# Sheet2.net
KiCad netlist of a schematic drawn in Altium Designer
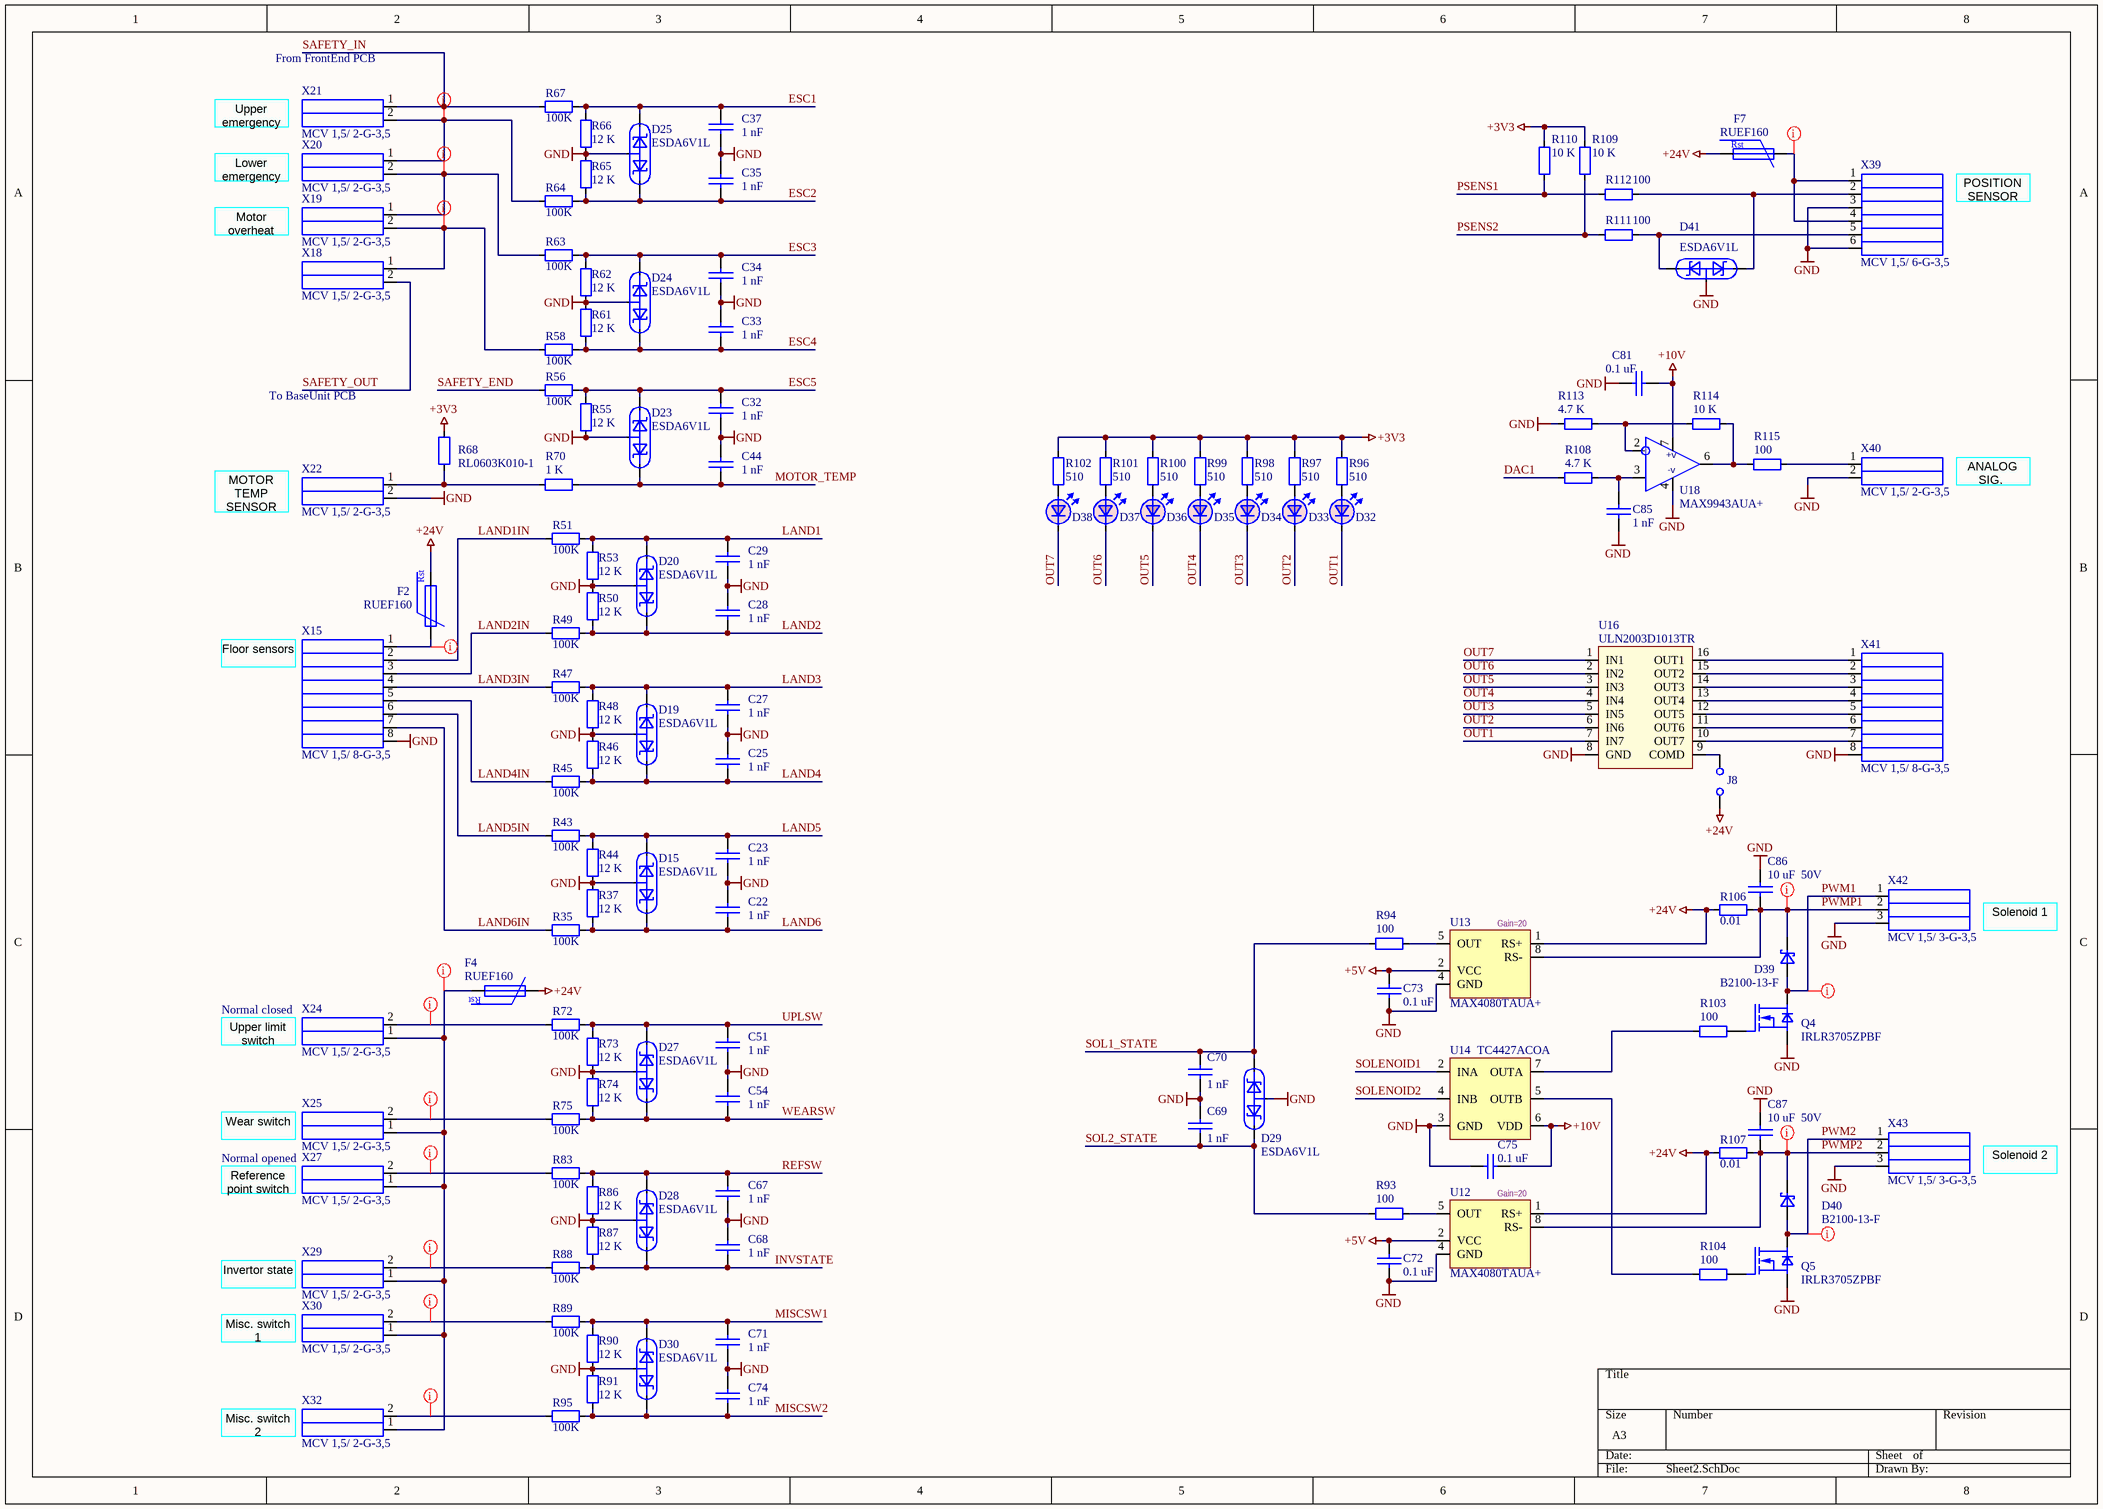
[diagram p0: Sheet2.SchDoc]

(export (version "E")
  (design (tool "Eeschema 10.0.6"))
  (components
    (comp (ref "C22")
      (value "1 nF")
      (footprint "1608[0603]")
      (description "1 nF, 50V, 10%, X7R, 0603 SMD MLC Capacitor")
      (fields (field (name "TOLERANCE") "+-10%") (field (name "MANUFACTURER") "Darfon"))
      (libsource (lib "ea_Capacitors") (part "CVNF1.0K0603"))
    )
    (comp (ref "C23")
      (value "1 nF")
      (footprint "1608[0603]")
      (description "1 nF, 50V, 10%, X7R, 0603 SMD MLC Capacitor")
      (fields (field (name "TOLERANCE") "+-10%") (field (name "MANUFACTURER") "Darfon"))
      (libsource (lib "ea_Capacitors") (part "CVNF1.0K0603"))
    )
    (comp (ref "C25")
      (value "1 nF")
      (footprint "1608[0603]")
      (description "1 nF, 50V, 10%, X7R, 0603 SMD MLC Capacitor")
      (fields (field (name "TOLERANCE") "+-10%") (field (name "MANUFACTURER") "Darfon"))
      (libsource (lib "ea_Capacitors") (part "CVNF1.0K0603"))
    )
    (comp (ref "C27")
      (value "1 nF")
      (footprint "1608[0603]")
      (description "1 nF, 50V, 10%, X7R, 0603 SMD MLC Capacitor")
      (fields (field (name "TOLERANCE") "+-10%") (field (name "MANUFACTURER") "Darfon"))
      (libsource (lib "ea_Capacitors") (part "CVNF1.0K0603"))
    )
    (comp (ref "C28")
      (value "1 nF")
      (footprint "1608[0603]")
      (description "1 nF, 50V, 10%, X7R, 0603 SMD MLC Capacitor")
      (fields (field (name "TOLERANCE") "+-10%") (field (name "MANUFACTURER") "Darfon"))
      (libsource (lib "ea_Capacitors") (part "CVNF1.0K0603"))
    )
    (comp (ref "C29")
      (value "1 nF")
      (footprint "1608[0603]")
      (description "1 nF, 50V, 10%, X7R, 0603 SMD MLC Capacitor")
      (fields (field (name "TOLERANCE") "+-10%") (field (name "MANUFACTURER") "Darfon"))
      (libsource (lib "ea_Capacitors") (part "CVNF1.0K0603"))
    )
    (comp (ref "C32")
      (value "1 nF")
      (footprint "1608[0603]")
      (description "1 nF, 50V, 10%, X7R, 0603 SMD MLC Capacitor")
      (fields (field (name "TOLERANCE") "+-10%") (field (name "MANUFACTURER") "Darfon"))
      (libsource (lib "ea_Capacitors") (part "CVNF1.0K0603"))
    )
    (comp (ref "C33")
      (value "1 nF")
      (footprint "1608[0603]")
      (description "1 nF, 50V, 10%, X7R, 0603 SMD MLC Capacitor")
      (fields (field (name "TOLERANCE") "+-10%") (field (name "MANUFACTURER") "Darfon"))
      (libsource (lib "ea_Capacitors") (part "CVNF1.0K0603"))
    )
    (comp (ref "C34")
      (value "1 nF")
      (footprint "1608[0603]")
      (description "1 nF, 50V, 10%, X7R, 0603 SMD MLC Capacitor")
      (fields (field (name "TOLERANCE") "+-10%") (field (name "MANUFACTURER") "Darfon"))
      (libsource (lib "ea_Capacitors") (part "CVNF1.0K0603"))
    )
    (comp (ref "C35")
      (value "1 nF")
      (footprint "1608[0603]")
      (description "1 nF, 50V, 10%, X7R, 0603 SMD MLC Capacitor")
      (fields (field (name "TOLERANCE") "+-10%") (field (name "MANUFACTURER") "Darfon"))
      (libsource (lib "ea_Capacitors") (part "CVNF1.0K0603"))
    )
    (comp (ref "C37")
      (value "1 nF")
      (footprint "1608[0603]")
      (description "1 nF, 50V, 10%, X7R, 0603 SMD MLC Capacitor")
      (fields (field (name "TOLERANCE") "+-10%") (field (name "MANUFACTURER") "Darfon"))
      (libsource (lib "ea_Capacitors") (part "CVNF1.0K0603"))
    )
    (comp (ref "C44")
      (value "1 nF")
      (footprint "1608[0603]")
      (description "1 nF, 50V, 10%, X7R, 0603 SMD MLC Capacitor")
      (fields (field (name "TOLERANCE") "+-10%") (field (name "MANUFACTURER") "Darfon"))
      (libsource (lib "ea_Capacitors") (part "CVNF1.0K0603"))
    )
    (comp (ref "C51")
      (value "1 nF")
      (footprint "1608[0603]")
      (description "1 nF, 50V, 10%, X7R, 0603 SMD MLC Capacitor")
      (fields (field (name "TOLERANCE") "+-10%") (field (name "MANUFACTURER") "Darfon"))
      (libsource (lib "ea_Capacitors") (part "CVNF1.0K0603"))
    )
    (comp (ref "C54")
      (value "1 nF")
      (footprint "1608[0603]")
      (description "1 nF, 50V, 10%, X7R, 0603 SMD MLC Capacitor")
      (fields (field (name "TOLERANCE") "+-10%") (field (name "MANUFACTURER") "Darfon"))
      (libsource (lib "ea_Capacitors") (part "CVNF1.0K0603"))
    )
    (comp (ref "C67")
      (value "1 nF")
      (footprint "1608[0603]")
      (description "1 nF, 50V, 10%, X7R, 0603 SMD MLC Capacitor")
      (fields (field (name "TOLERANCE") "+-10%") (field (name "MANUFACTURER") "Darfon"))
      (libsource (lib "ea_Capacitors") (part "CVNF1.0K0603"))
    )
    (comp (ref "C68")
      (value "1 nF")
      (footprint "1608[0603]")
      (description "1 nF, 50V, 10%, X7R, 0603 SMD MLC Capacitor")
      (fields (field (name "TOLERANCE") "+-10%") (field (name "MANUFACTURER") "Darfon"))
      (libsource (lib "ea_Capacitors") (part "CVNF1.0K0603"))
    )
    (comp (ref "C69")
      (value "1 nF")
      (footprint "1608[0603]")
      (description "1 nF, 50V, 10%, X7R, 0603 SMD MLC Capacitor")
      (fields (field (name "TOLERANCE") "+-10%") (field (name "MANUFACTURER") "Darfon"))
      (libsource (lib "ea_Capacitors") (part "CVNF1.0K0603"))
    )
    (comp (ref "C70")
      (value "1 nF")
      (footprint "1608[0603]")
      (description "1 nF, 50V, 10%, X7R, 0603 SMD MLC Capacitor")
      (fields (field (name "TOLERANCE") "+-10%") (field (name "MANUFACTURER") "Darfon"))
      (libsource (lib "ea_Capacitors") (part "CVNF1.0K0603"))
    )
    (comp (ref "C71")
      (value "1 nF")
      (footprint "1608[0603]")
      (description "1 nF, 50V, 10%, X7R, 0603 SMD MLC Capacitor")
      (fields (field (name "TOLERANCE") "+-10%") (field (name "MANUFACTURER") "Darfon"))
      (libsource (lib "ea_Capacitors") (part "CVNF1.0K0603"))
    )
    (comp (ref "C72")
      (value "0.1 uF")
      (footprint "1608[0603]")
      (description "0.1 uF, 25V, 10% , X7R,  0603 SMD MLC Capacitor")
      (fields (field (name "TOLERANCE") "10%") (field (name "MANUFACTURER") "SAMSUNG"))
      (libsource (lib "ea_Capacitors") (part "CVNF100K0603-25"))
    )
    (comp (ref "C73")
      (value "0.1 uF")
      (footprint "1608[0603]")
      (description "0.1 uF, 25V, 10% , X7R,  0603 SMD MLC Capacitor")
      (fields (field (name "TOLERANCE") "10%") (field (name "MANUFACTURER") "SAMSUNG"))
      (libsource (lib "ea_Capacitors") (part "CVNF100K0603-25"))
    )
    (comp (ref "C74")
      (value "1 nF")
      (footprint "1608[0603]")
      (description "1 nF, 50V, 10%, X7R, 0603 SMD MLC Capacitor")
      (fields (field (name "TOLERANCE") "+-10%") (field (name "MANUFACTURER") "Darfon"))
      (libsource (lib "ea_Capacitors") (part "CVNF1.0K0603"))
    )
    (comp (ref "C75")
      (value "0.1 uF")
      (footprint "1608[0603]")
      (description "0.1 uF, 25V, 10% , X7R,  0603 SMD MLC Capacitor")
      (fields (field (name "TOLERANCE") "10%") (field (name "MANUFACTURER") "SAMSUNG"))
      (libsource (lib "ea_Capacitors") (part "CVNF100K0603-25"))
    )
    (comp (ref "C81")
      (value "0.1 uF")
      (footprint "1608[0603]")
      (description "0.1 uF, 25V, 10% , X7R,  0603 SMD MLC Capacitor")
      (fields (field (name "TOLERANCE") "10%") (field (name "MANUFACTURER") "SAMSUNG"))
      (libsource (lib "ea_Capacitors") (part "CVNF100K0603-25"))
    )
    (comp (ref "C85")
      (value "1 nF")
      (footprint "1608[0603]")
      (description "1 nF, 50V, 10%, X7R, 0603 SMD MLC Capacitor")
      (fields (field (name "TOLERANCE") "+-10%") (field (name "MANUFACTURER") "Darfon"))
      (libsource (lib "ea_Capacitors") (part "CVNF1.0K0603"))
    )
    (comp (ref "C86")
      (value "10 uF")
      (footprint "3225[1210]")
      (description "10uF, 50V, 20%, Y5V (F), 1210")
      (fields
        (field (name "MANUFACTURER") "Taiyo Yuden")
        (field (name "TOLERANCE") "20%")
        (field (name "VOLTAGE") "50V")
      )
      (libsource (lib "ea_Capacitors") (part "GRM32DF51H106ZA01L"))
    )
    (comp (ref "C87")
      (value "10 uF")
      (footprint "3225[1210]")
      (description "10uF, 50V, 20%, Y5V (F), 1210")
      (fields
        (field (name "MANUFACTURER") "Taiyo Yuden")
        (field (name "TOLERANCE") "20%")
        (field (name "VOLTAGE") "50V")
      )
      (libsource (lib "ea_Capacitors") (part "GRM32DF51H106ZA01L"))
    )
    (comp (ref "D15")
      (value "ESDA6V1L")
      (footprint "SOT23")
      (description "Dual transil array for ESD, 6.1 V, 300 W")
      (fields (field (name "MANUFACTURER") "Micro Commercial Co") (field (name "PARTNUM") "ESDA6V1L-TPCT-ND"))
      (libsource (lib "") (part "ESDA6V1L_1"))
    )
    (comp (ref "D19")
      (value "ESDA6V1L")
      (footprint "SOT23")
      (description "Dual transil array for ESD, 6.1 V, 300 W")
      (fields (field (name "MANUFACTURER") "Micro Commercial Co") (field (name "PARTNUM") "ESDA6V1L-TPCT-ND"))
      (libsource (lib "") (part "ESDA6V1L_1"))
    )
    (comp (ref "D20")
      (value "ESDA6V1L")
      (footprint "SOT23")
      (description "Dual transil array for ESD, 6.1 V, 300 W")
      (fields (field (name "MANUFACTURER") "Micro Commercial Co") (field (name "PARTNUM") "ESDA6V1L-TPCT-ND"))
      (libsource (lib "") (part "ESDA6V1L_1"))
    )
    (comp (ref "D23")
      (value "ESDA6V1L")
      (footprint "SOT23")
      (description "Dual transil array for ESD, 6.1 V, 300 W")
      (fields (field (name "MANUFACTURER") "Micro Commercial Co") (field (name "PARTNUM") "ESDA6V1L-TPCT-ND"))
      (libsource (lib "") (part "ESDA6V1L_1"))
    )
    (comp (ref "D24")
      (value "ESDA6V1L")
      (footprint "SOT23")
      (description "Dual transil array for ESD, 6.1 V, 300 W")
      (fields (field (name "MANUFACTURER") "Micro Commercial Co") (field (name "PARTNUM") "ESDA6V1L-TPCT-ND"))
      (libsource (lib "") (part "ESDA6V1L_1"))
    )
    (comp (ref "D25")
      (value "ESDA6V1L")
      (footprint "SOT23")
      (description "Dual transil array for ESD, 6.1 V, 300 W")
      (fields (field (name "MANUFACTURER") "Micro Commercial Co") (field (name "PARTNUM") "ESDA6V1L-TPCT-ND"))
      (libsource (lib "") (part "ESDA6V1L_1"))
    )
    (comp (ref "D27")
      (value "ESDA6V1L")
      (footprint "SOT23")
      (description "Dual transil array for ESD, 6.1 V, 300 W")
      (fields (field (name "MANUFACTURER") "Micro Commercial Co") (field (name "PARTNUM") "ESDA6V1L-TPCT-ND"))
      (libsource (lib "*") (part "ESDA6V1L"))
    )
    (comp (ref "D28")
      (value "ESDA6V1L")
      (footprint "SOT23")
      (description "Dual transil array for ESD, 6.1 V, 300 W")
      (fields (field (name "MANUFACTURER") "Micro Commercial Co") (field (name "PARTNUM") "ESDA6V1L-TPCT-ND"))
      (libsource (lib "*") (part "ESDA6V1L"))
    )
    (comp (ref "D29")
      (value "ESDA6V1L")
      (footprint "SOT23")
      (description "Dual transil array for ESD, 6.1 V, 300 W")
      (fields (field (name "MANUFACTURER") "Micro Commercial Co") (field (name "PARTNUM") "ESDA6V1L-TPCT-ND"))
      (libsource (lib "*") (part "ESDA6V1L"))
    )
    (comp (ref "D30")
      (value "ESDA6V1L")
      (footprint "SOT23")
      (description "Dual transil array for ESD, 6.1 V, 300 W")
      (fields (field (name "MANUFACTURER") "Micro Commercial Co") (field (name "PARTNUM") "ESDA6V1L-TPCT-ND"))
      (libsource (lib "*") (part "ESDA6V1L"))
    )
    (comp (ref "D32")
      (value "SML-211UTT86")
      (footprint "0805 LED")
      (description "0805 red LED, hibright, 2 mA, 1.8V, 130°")
      (fields (field (name "MANUFACTURER") "Rohm") (field (name "PARTNUM") "511-1292-1-ND"))
      (libsource (lib "ea_Indicators") (part "SML-211UTT86"))
    )
    (comp (ref "D33")
      (value "SML-211UTT86")
      (footprint "0805 LED")
      (description "0805 red LED, hibright, 2 mA, 1.8V, 130°")
      (fields (field (name "MANUFACTURER") "Rohm") (field (name "PARTNUM") "511-1292-1-ND"))
      (libsource (lib "ea_Indicators") (part "SML-211UTT86"))
    )
    (comp (ref "D34")
      (value "SML-211UTT86")
      (footprint "0805 LED")
      (description "0805 red LED, hibright, 2 mA, 1.8V, 130°")
      (fields (field (name "MANUFACTURER") "Rohm") (field (name "PARTNUM") "511-1292-1-ND"))
      (libsource (lib "ea_Indicators") (part "SML-211UTT86"))
    )
    (comp (ref "D35")
      (value "SML-211UTT86")
      (footprint "0805 LED")
      (description "0805 red LED, hibright, 2 mA, 1.8V, 130°")
      (fields (field (name "MANUFACTURER") "Rohm") (field (name "PARTNUM") "511-1292-1-ND"))
      (libsource (lib "ea_Indicators") (part "SML-211UTT86"))
    )
    (comp (ref "D36")
      (value "SML-211UTT86")
      (footprint "0805 LED")
      (description "0805 red LED, hibright, 2 mA, 1.8V, 130°")
      (fields (field (name "MANUFACTURER") "Rohm") (field (name "PARTNUM") "511-1292-1-ND"))
      (libsource (lib "ea_Indicators") (part "SML-211UTT86"))
    )
    (comp (ref "D37")
      (value "SML-211UTT86")
      (footprint "0805 LED")
      (description "0805 red LED, hibright, 2 mA, 1.8V, 130°")
      (fields (field (name "MANUFACTURER") "Rohm") (field (name "PARTNUM") "511-1292-1-ND"))
      (libsource (lib "ea_Indicators") (part "SML-211UTT86"))
    )
    (comp (ref "D38")
      (value "SML-211UTT86")
      (footprint "0805 LED")
      (description "0805 red LED, hibright, 2 mA, 1.8V, 130°")
      (fields (field (name "MANUFACTURER") "Rohm") (field (name "PARTNUM") "511-1292-1-ND"))
      (libsource (lib "ea_Indicators") (part "SML-211UTT86"))
    )
    (comp (ref "D39")
      (value "B2100-13-F")
      (footprint "SMB ST")
      (description "DIODE SCHOTTKY 100V 2A SMB")
      (fields (field (name "MANUFACTURER") "Diodes Inc") (field (name "PARTNUM") "B2100-FDICT-ND"))
      (libsource (lib "ea_Diodes") (part "B2100-13-F"))
    )
    (comp (ref "D40")
      (value "B2100-13-F")
      (footprint "SMB ST")
      (description "DIODE SCHOTTKY 100V 2A SMB")
      (fields (field (name "MANUFACTURER") "Diodes Inc") (field (name "PARTNUM") "B2100-FDICT-ND"))
      (libsource (lib "ea_Diodes") (part "B2100-13-F"))
    )
    (comp (ref "D41")
      (value "ESDA6V1L")
      (footprint "SOT23")
      (description "Dual transil array for ESD, 6.1 V, 300 W")
      (fields (field (name "MANUFACTURER") "Micro Commercial Co") (field (name "PARTNUM") "ESDA6V1L-TPCT-ND"))
      (libsource (lib "*") (part "ESDA6V1L"))
    )
    (comp (ref "F2")
      (value "RUEF160")
      (footprint "RUE160")
      (description "RUEF160 - POLYSWITCH, RADIAL, 1.6A")
      (fields (field (name "MANUFACTURER") "RAYCHEM") (field (name "PARTNUM") "RUEF160-ND"))
      (libsource (lib "ea_Fuses") (part "RUEF160"))
    )
    (comp (ref "F4")
      (value "RUEF160")
      (footprint "RUE160")
      (description "RUEF160 - POLYSWITCH, RADIAL, 1.6A")
      (fields (field (name "MANUFACTURER") "RAYCHEM") (field (name "PARTNUM") "RUEF160-ND"))
      (libsource (lib "ea_Fuses") (part "RUEF160"))
    )
    (comp (ref "F7")
      (value "RUEF160")
      (footprint "RUE160")
      (description "RUEF160 - POLYSWITCH, RADIAL, 1.6A")
      (fields (field (name "MANUFACTURER") "RAYCHEM") (field (name "PARTNUM") "RUEF160-ND"))
      (libsource (lib "ea_Fuses") (part "RUEF160"))
    )
    (comp (ref "J8")
      (value "PH1-02-TA-HT")
      (footprint "HDR1X2V")
      (description "2 Pos. 2.54 mm Single Row Through Hole Straight Pin Header")
      (fields (field (name "MANUFACTURER") "ADAM TECH"))
      (libsource (lib "ea_Commutation") (part "Jumper"))
    )
    (comp (ref "Q4")
      (value "IRLR3705ZPBF")
      (footprint "DPAK TO-252")
      (description "MOSFET N-CH 55V 42A DPAK")
      (fields
        (field (name "MANUFACTURER") "International Rectifier")
        (field (name "PARTNUM") "IRLR3705ZPBF-ND")
      )
      (libsource (lib "ea_MOSFET_&_drivers") (part "IRLR3705ZPBF"))
    )
    (comp (ref "Q5")
      (value "IRLR3705ZPBF")
      (footprint "DPAK TO-252")
      (description "MOSFET N-CH 55V 42A DPAK")
      (fields
        (field (name "MANUFACTURER") "International Rectifier")
        (field (name "PARTNUM") "IRLR3705ZPBF-ND")
      )
      (libsource (lib "ea_MOSFET_&_drivers") (part "IRLR3705ZPBF"))
    )
    (comp (ref "R35")
      (value "100K")
      (footprint "3216[1206]")
      (description "100K, 1%,  1206,  200v,  SMD 1206")
      (fields (field (name "MANUFACTURER") "Panasonic") (field (name "TOLERANCE") "1%"))
      (libsource (lib "ea_Resistors") (part "CRCW1206100KFKEA"))
    )
    (comp (ref "R37")
      (value "12 K")
      (footprint "0603")
      (description "12 K, 1%, 0603, SMD Resistor, Taped")
      (fields (field (name "MANUFACTURER") "Vishay") (field (name "TOLERANCE") "1%"))
      (libsource (lib "ea_Resistors") (part "RL0603K012-1"))
    )
    (comp (ref "R43")
      (value "100K")
      (footprint "3216[1206]")
      (description "100K, 1%,  1206,  200v,  SMD 1206")
      (fields (field (name "MANUFACTURER") "Panasonic") (field (name "TOLERANCE") "1%"))
      (libsource (lib "ea_Resistors") (part "CRCW1206100KFKEA"))
    )
    (comp (ref "R44")
      (value "12 K")
      (footprint "0603")
      (description "12 K, 1%, 0603, SMD Resistor, Taped")
      (fields (field (name "MANUFACTURER") "Vishay") (field (name "TOLERANCE") "1%"))
      (libsource (lib "ea_Resistors") (part "RL0603K012-1"))
    )
    (comp (ref "R45")
      (value "100K")
      (footprint "3216[1206]")
      (description "100K, 1%,  1206,  200v,  SMD 1206")
      (fields (field (name "MANUFACTURER") "Panasonic") (field (name "TOLERANCE") "1%"))
      (libsource (lib "ea_Resistors") (part "CRCW1206100KFKEA"))
    )
    (comp (ref "R46")
      (value "12 K")
      (footprint "0603")
      (description "12 K, 1%, 0603, SMD Resistor, Taped")
      (fields (field (name "MANUFACTURER") "Vishay") (field (name "TOLERANCE") "1%"))
      (libsource (lib "ea_Resistors") (part "RL0603K012-1"))
    )
    (comp (ref "R47")
      (value "100K")
      (footprint "3216[1206]")
      (description "100K, 1%,  1206,  200v,  SMD 1206")
      (fields (field (name "MANUFACTURER") "Panasonic") (field (name "TOLERANCE") "1%"))
      (libsource (lib "ea_Resistors") (part "CRCW1206100KFKEA"))
    )
    (comp (ref "R48")
      (value "12 K")
      (footprint "0603")
      (description "12 K, 1%, 0603, SMD Resistor, Taped")
      (fields (field (name "MANUFACTURER") "Vishay") (field (name "TOLERANCE") "1%"))
      (libsource (lib "ea_Resistors") (part "RL0603K012-1"))
    )
    (comp (ref "R49")
      (value "100K")
      (footprint "3216[1206]")
      (description "100K, 1%,  1206,  200v,  SMD 1206")
      (fields (field (name "MANUFACTURER") "Panasonic") (field (name "TOLERANCE") "1%"))
      (libsource (lib "ea_Resistors") (part "CRCW1206100KFKEA"))
    )
    (comp (ref "R50")
      (value "12 K")
      (footprint "0603")
      (description "12 K, 1%, 0603, SMD Resistor, Taped")
      (fields (field (name "MANUFACTURER") "Vishay") (field (name "TOLERANCE") "1%"))
      (libsource (lib "ea_Resistors") (part "RL0603K012-1"))
    )
    (comp (ref "R51")
      (value "100K")
      (footprint "3216[1206]")
      (description "100K, 1%,  1206,  200v,  SMD 1206")
      (fields (field (name "MANUFACTURER") "Panasonic") (field (name "TOLERANCE") "1%"))
      (libsource (lib "ea_Resistors") (part "CRCW1206100KFKEA"))
    )
    (comp (ref "R53")
      (value "12 K")
      (footprint "0603")
      (description "12 K, 1%, 0603, SMD Resistor, Taped")
      (fields (field (name "MANUFACTURER") "Vishay") (field (name "TOLERANCE") "1%"))
      (libsource (lib "ea_Resistors") (part "RL0603K012-1"))
    )
    (comp (ref "R55")
      (value "12 K")
      (footprint "0603")
      (description "12 K, 1%, 0603, SMD Resistor, Taped")
      (fields (field (name "MANUFACTURER") "Vishay") (field (name "TOLERANCE") "1%"))
      (libsource (lib "ea_Resistors") (part "RL0603K012-1"))
    )
    (comp (ref "R56")
      (value "100K")
      (footprint "3216[1206]")
      (description "100K, 1%,  1206,  200v,  SMD 1206")
      (fields (field (name "MANUFACTURER") "Panasonic") (field (name "TOLERANCE") "1%"))
      (libsource (lib "ea_Resistors") (part "CRCW1206100KFKEA"))
    )
    (comp (ref "R58")
      (value "100K")
      (footprint "3216[1206]")
      (description "100K, 1%,  1206,  200v,  SMD 1206")
      (fields (field (name "MANUFACTURER") "Panasonic") (field (name "TOLERANCE") "1%"))
      (libsource (lib "ea_Resistors") (part "CRCW1206100KFKEA"))
    )
    (comp (ref "R61")
      (value "12 K")
      (footprint "0603")
      (description "12 K, 1%, 0603, SMD Resistor, Taped")
      (fields (field (name "MANUFACTURER") "Vishay") (field (name "TOLERANCE") "1%"))
      (libsource (lib "ea_Resistors") (part "RL0603K012-1"))
    )
    (comp (ref "R62")
      (value "12 K")
      (footprint "0603")
      (description "12 K, 1%, 0603, SMD Resistor, Taped")
      (fields (field (name "MANUFACTURER") "Vishay") (field (name "TOLERANCE") "1%"))
      (libsource (lib "ea_Resistors") (part "RL0603K012-1"))
    )
    (comp (ref "R63")
      (value "100K")
      (footprint "3216[1206]")
      (description "100K, 1%,  1206,  200v,  SMD 1206")
      (fields (field (name "MANUFACTURER") "Panasonic") (field (name "TOLERANCE") "1%"))
      (libsource (lib "ea_Resistors") (part "CRCW1206100KFKEA"))
    )
    (comp (ref "R64")
      (value "100K")
      (footprint "3216[1206]")
      (description "100K, 1%,  1206,  200v,  SMD 1206")
      (fields (field (name "MANUFACTURER") "Panasonic") (field (name "TOLERANCE") "1%"))
      (libsource (lib "ea_Resistors") (part "CRCW1206100KFKEA"))
    )
    (comp (ref "R65")
      (value "12 K")
      (footprint "0603")
      (description "12 K, 1%, 0603, SMD Resistor, Taped")
      (fields (field (name "MANUFACTURER") "Vishay") (field (name "TOLERANCE") "1%"))
      (libsource (lib "ea_Resistors") (part "RL0603K012-1"))
    )
    (comp (ref "R66")
      (value "12 K")
      (footprint "0603")
      (description "12 K, 1%, 0603, SMD Resistor, Taped")
      (fields (field (name "MANUFACTURER") "Vishay") (field (name "TOLERANCE") "1%"))
      (libsource (lib "ea_Resistors") (part "RL0603K012-1"))
    )
    (comp (ref "R67")
      (value "100K")
      (footprint "3216[1206]")
      (description "100K, 1%,  1206,  200v,  SMD 1206")
      (fields (field (name "MANUFACTURER") "Panasonic") (field (name "TOLERANCE") "1%"))
      (libsource (lib "ea_Resistors") (part "CRCW1206100KFKEA"))
    )
    (comp (ref "R68")
      (value "RL0603K010-1")
      (footprint "0603")
      (description "10 K, 1%, 0603, SMD Resistor, Taped")
      (fields (field (name "MANUFACTURER") "Vishay Dale") (field (name "TOLERANCE") "1%"))
      (libsource (lib "") (part "RL0603K010-1_2"))
    )
    (comp (ref "R70")
      (value "1 K")
      (footprint "0603")
      (description "1 K, 1%, 0603, SMD Resistor, Taped")
      (fields (field (name "MANUFACTURER") "YAGEO AMERICA CORPORATION") (field (name "TOLERANCE") "1%"))
      (libsource (lib "ea_Resistors") (part "RL0603K001-1"))
    )
    (comp (ref "R72")
      (value "100K")
      (footprint "3216[1206]")
      (description "100K, 1%,  1206,  200v,  SMD 1206")
      (fields (field (name "MANUFACTURER") "Panasonic") (field (name "TOLERANCE") "1%"))
      (libsource (lib "ea_Resistors") (part "CRCW1206100KFKEA"))
    )
    (comp (ref "R73")
      (value "12 K")
      (footprint "0603")
      (description "12 K, 1%, 0603, SMD Resistor, Taped")
      (fields (field (name "MANUFACTURER") "Vishay") (field (name "TOLERANCE") "1%"))
      (libsource (lib "ea_Resistors") (part "RL0603K012-1"))
    )
    (comp (ref "R74")
      (value "12 K")
      (footprint "0603")
      (description "12 K, 1%, 0603, SMD Resistor, Taped")
      (fields (field (name "MANUFACTURER") "Vishay") (field (name "TOLERANCE") "1%"))
      (libsource (lib "ea_Resistors") (part "RL0603K012-1"))
    )
    (comp (ref "R75")
      (value "100K")
      (footprint "3216[1206]")
      (description "100K, 1%,  1206,  200v,  SMD 1206")
      (fields (field (name "MANUFACTURER") "Panasonic") (field (name "TOLERANCE") "1%"))
      (libsource (lib "ea_Resistors") (part "CRCW1206100KFKEA"))
    )
    (comp (ref "R83")
      (value "100K")
      (footprint "3216[1206]")
      (description "100K, 1%,  1206,  200v,  SMD 1206")
      (fields (field (name "MANUFACTURER") "Panasonic") (field (name "TOLERANCE") "1%"))
      (libsource (lib "ea_Resistors") (part "CRCW1206100KFKEA"))
    )
    (comp (ref "R86")
      (value "12 K")
      (footprint "0603")
      (description "12 K, 1%, 0603, SMD Resistor, Taped")
      (fields (field (name "MANUFACTURER") "Vishay") (field (name "TOLERANCE") "1%"))
      (libsource (lib "ea_Resistors") (part "RL0603K012-1"))
    )
    (comp (ref "R87")
      (value "12 K")
      (footprint "0603")
      (description "12 K, 1%, 0603, SMD Resistor, Taped")
      (fields (field (name "MANUFACTURER") "Vishay") (field (name "TOLERANCE") "1%"))
      (libsource (lib "ea_Resistors") (part "RL0603K012-1"))
    )
    (comp (ref "R88")
      (value "100K")
      (footprint "3216[1206]")
      (description "100K, 1%,  1206,  200v,  SMD 1206")
      (fields (field (name "MANUFACTURER") "Panasonic") (field (name "TOLERANCE") "1%"))
      (libsource (lib "ea_Resistors") (part "CRCW1206100KFKEA"))
    )
    (comp (ref "R89")
      (value "100K")
      (footprint "3216[1206]")
      (description "100K, 1%,  1206,  200v,  SMD 1206")
      (fields (field (name "MANUFACTURER") "Panasonic") (field (name "TOLERANCE") "1%"))
      (libsource (lib "ea_Resistors") (part "CRCW1206100KFKEA"))
    )
    (comp (ref "R90")
      (value "12 K")
      (footprint "0603")
      (description "12 K, 1%, 0603, SMD Resistor, Taped")
      (fields (field (name "MANUFACTURER") "Vishay") (field (name "TOLERANCE") "1%"))
      (libsource (lib "ea_Resistors") (part "RL0603K012-1"))
    )
    (comp (ref "R91")
      (value "12 K")
      (footprint "0603")
      (description "12 K, 1%, 0603, SMD Resistor, Taped")
      (fields (field (name "MANUFACTURER") "Vishay") (field (name "TOLERANCE") "1%"))
      (libsource (lib "ea_Resistors") (part "RL0603K012-1"))
    )
    (comp (ref "R93")
      (value "100")
      (footprint "0603")
      (description "100, 1%, 0603, SMD Resistor, Taped")
      (fields (field (name "TOLERANCE") "1%") (field (name "MANUFACTURER") "PANASONIC"))
      (libsource (lib "ea_Resistors") (part "RL0603E100-1"))
    )
    (comp (ref "R94")
      (value "100")
      (footprint "0603")
      (description "100, 1%, 0603, SMD Resistor, Taped")
      (fields (field (name "TOLERANCE") "1%") (field (name "MANUFACTURER") "PANASONIC"))
      (libsource (lib "ea_Resistors") (part "RL0603E100-1"))
    )
    (comp (ref "R95")
      (value "100K")
      (footprint "3216[1206]")
      (description "100K, 1%,  1206,  200v,  SMD 1206")
      (fields (field (name "MANUFACTURER") "Panasonic") (field (name "TOLERANCE") "1%"))
      (libsource (lib "ea_Resistors") (part "CRCW1206100KFKEA"))
    )
    (comp (ref "R96")
      (value "510")
      (footprint "0603")
      (description "510 R, 1%, 0603, SMD Resistor, Taped")
      (fields (field (name "MANUFACTURER") "Vishay") (field (name "TOLERANCE") "1%"))
      (libsource (lib "ea_Resistors") (part "RL0603E510-1"))
    )
    (comp (ref "R97")
      (value "510")
      (footprint "0603")
      (description "510 R, 1%, 0603, SMD Resistor, Taped")
      (fields (field (name "MANUFACTURER") "Vishay") (field (name "TOLERANCE") "1%"))
      (libsource (lib "ea_Resistors") (part "RL0603E510-1"))
    )
    (comp (ref "R98")
      (value "510")
      (footprint "0603")
      (description "510 R, 1%, 0603, SMD Resistor, Taped")
      (fields (field (name "MANUFACTURER") "Vishay") (field (name "TOLERANCE") "1%"))
      (libsource (lib "ea_Resistors") (part "RL0603E510-1"))
    )
    (comp (ref "R99")
      (value "510")
      (footprint "0603")
      (description "510 R, 1%, 0603, SMD Resistor, Taped")
      (fields (field (name "MANUFACTURER") "Vishay") (field (name "TOLERANCE") "1%"))
      (libsource (lib "ea_Resistors") (part "RL0603E510-1"))
    )
    (comp (ref "R100")
      (value "510")
      (footprint "0603")
      (description "510 R, 1%, 0603, SMD Resistor, Taped")
      (fields (field (name "MANUFACTURER") "Vishay") (field (name "TOLERANCE") "1%"))
      (libsource (lib "ea_Resistors") (part "RL0603E510-1"))
    )
    (comp (ref "R101")
      (value "510")
      (footprint "0603")
      (description "510 R, 1%, 0603, SMD Resistor, Taped")
      (fields (field (name "MANUFACTURER") "Vishay") (field (name "TOLERANCE") "1%"))
      (libsource (lib "ea_Resistors") (part "RL0603E510-1"))
    )
    (comp (ref "R102")
      (value "510")
      (footprint "0603")
      (description "510 R, 1%, 0603, SMD Resistor, Taped")
      (fields (field (name "MANUFACTURER") "Vishay") (field (name "TOLERANCE") "1%"))
      (libsource (lib "ea_Resistors") (part "RL0603E510-1"))
    )
    (comp (ref "R103")
      (value "100")
      (footprint "0603")
      (description "100, 1%, 0603, SMD Resistor, Taped")
      (fields (field (name "TOLERANCE") "1%") (field (name "MANUFACTURER") "PANASONIC"))
      (libsource (lib "ea_Resistors") (part "RL0603E100-1"))
    )
    (comp (ref "R104")
      (value "100")
      (footprint "0603")
      (description "100, 1%, 0603, SMD Resistor, Taped")
      (fields (field (name "TOLERANCE") "1%") (field (name "MANUFACTURER") "PANASONIC"))
      (libsource (lib "ea_Resistors") (part "RL0603E100-1"))
    )
    (comp (ref "R106")
      (value "0.01")
      (footprint "MCS3264")
      (description "Curr.sens.res. 0.01 OHM 2W 1% , 2512 (6432 Metric)")
      (fields (field (name "MANUFACTURER") "Ohmite") (field (name "TOLERANCE") "1%"))
      (libsource (lib "ea_Resistors") (part "MCS3264R010FER"))
    )
    (comp (ref "R107")
      (value "0.01")
      (footprint "MCS3264")
      (description "Curr.sens.res. 0.01 OHM 2W 1% , 2512 (6432 Metric)")
      (fields (field (name "MANUFACTURER") "Ohmite") (field (name "TOLERANCE") "1%"))
      (libsource (lib "ea_Resistors") (part "MCS3264R010FER"))
    )
    (comp (ref "R108")
      (value "4.7 K")
      (footprint "0603")
      (description "4.7 K, 1%, 0603, SMD Resistor, Taped")
      (fields (field (name "MANUFACTURER") "Vishay") (field (name "TOLERANCE") "1%"))
      (libsource (lib "ea_Resistors") (part "RL0603K004.7-1"))
    )
    (comp (ref "R109")
      (value "10 K")
      (footprint "0603")
      (description "10 K, 1%, 0603, SMD Resistor, Taped")
      (fields (field (name "MANUFACTURER") "Vishay Dale") (field (name "TOLERANCE") "1%"))
      (libsource (lib "ea_Resistors") (part "RL0603K010-1"))
    )
    (comp (ref "R110")
      (value "10 K")
      (footprint "0603")
      (description "10 K, 1%, 0603, SMD Resistor, Taped")
      (fields (field (name "MANUFACTURER") "Vishay Dale") (field (name "TOLERANCE") "1%"))
      (libsource (lib "ea_Resistors") (part "RL0603K010-1"))
    )
    (comp (ref "R111")
      (value "100")
      (footprint "0603")
      (description "100, 1%, 0603, SMD Resistor, Taped")
      (fields (field (name "TOLERANCE") "1%") (field (name "MANUFACTURER") "PANASONIC"))
      (libsource (lib "") (part "RL0603E100-1_1"))
    )
    (comp (ref "R112")
      (value "100")
      (footprint "0603")
      (description "100, 1%, 0603, SMD Resistor, Taped")
      (fields (field (name "TOLERANCE") "1%") (field (name "MANUFACTURER") "PANASONIC"))
      (libsource (lib "") (part "RL0603E100-1_1"))
    )
    (comp (ref "R113")
      (value "4.7 K")
      (footprint "0603")
      (description "4.7 K, 1%, 0603, SMD Resistor, Taped")
      (fields (field (name "MANUFACTURER") "Vishay") (field (name "TOLERANCE") "1%"))
      (libsource (lib "ea_Resistors") (part "RL0603K004.7-1"))
    )
    (comp (ref "R114")
      (value "10 K")
      (footprint "0603")
      (description "10 K, 1%, 0603, SMD Resistor, Taped")
      (fields (field (name "MANUFACTURER") "Vishay Dale") (field (name "TOLERANCE") "1%"))
      (libsource (lib "") (part "RL0603K010-1_1"))
    )
    (comp (ref "R115")
      (value "100")
      (footprint "0603")
      (description "100, 1%, 0603, SMD Resistor, Taped")
      (fields (field (name "TOLERANCE") "1%") (field (name "MANUFACTURER") "PANASONIC"))
      (libsource (lib "") (part "RL0603E100-1_1"))
    )
    (comp (ref "U12")
      (value "MAX4080TAUA+")
      (footprint "MSOP 8")
      (description "IC OPAMP CURR SENSE 250KHZ 8UMAX")
      (fields (field (name "MANUFACTURER") "Infineon") (field (name "PARTNUM") "MAX4080TAUA+-ND"))
      (libsource (lib "ea_IC_sensors") (part "MAX4080TAUA+"))
    )
    (comp (ref "U13")
      (value "MAX4080TAUA+")
      (footprint "MSOP 8")
      (description "IC OPAMP CURR SENSE 250KHZ 8UMAX")
      (fields (field (name "MANUFACTURER") "Infineon") (field (name "PARTNUM") "MAX4080TAUA+-ND"))
      (libsource (lib "ea_IC_sensors") (part "MAX4080TAUA+"))
    )
    (comp (ref "U14")
      (value "TC4427ACOA")
      (footprint "SO-8")
      (description "MOSFET drv 1.5A dual, 4.5-18 V,   8SOIC, 0-70 C")
      (fields (field (name "MANUFACTURER") "Microchip Technology") (field (name "PARTNUM") "TC4427ACOA-ND"))
      (libsource (lib "ea_IC_registers_buffers") (part "TC4427ACOA"))
    )
    (comp (ref "U16")
      (value "ULN2003D1013TR")
      (footprint "SO-16")
      (description "TRANS 7 NPN DARL 50V 500MA 16SO")
      (fields (field (name "MANUFACTURER") "STMicroelectronics") (field (name "PARTNUM") "497-2345-1-ND"))
      (libsource (lib "ea_IC_registers_buffers") (part "ULN2003D1013TR"))
    )
    (comp (ref "U18")
      (value "MAX9943AUA+")
      (footprint "TSSOP-8")
      (description "OpAmp 2.4MHZ, 6..38V,  20 mA, 8-TSSOP")
      (fields
        (field (name "MANUFACTURER") "Maxim Integrated Products")
        (field (name "PARTNUM") "MAX9943AUA+-ND")
      )
      (libsource (lib "ea_IC_OPAmps_AnComparators") (part "MAX9943AUA+"))
    )
    (comp (ref "X15")
      (value "MCV 1,5/ 8-G-3,5")
      (footprint "mcv1.5-8-g_3.5")
      (description "HEADER, VERTICAL, 3.5MM, 8WAY")
      (fields (field (name "MANUFACTURER") "PHOENIX CONTACT") (field (name "PARTNUM") "1843664"))
      (libsource (lib "ea_Connectors") (part "MCV1.5/8-G-3.5"))
    )
    (comp (ref "X18")
      (value "MCV 1,5/ 2-G-3,5")
      (footprint "mcv1.5-2-g_3.5")
      (description "HEADER, VERTICAL, 3.5MM, 2WAY")
      (fields (field (name "MANUFACTURER") "PHOENIX CONTACT") (field (name "PARTNUM") "1843606"))
      (libsource (lib "ea_Connectors") (part "MCV1.5/2-G-3.5"))
    )
    (comp (ref "X19")
      (value "MCV 1,5/ 2-G-3,5")
      (footprint "mcv1.5-2-g_3.5")
      (description "HEADER, VERTICAL, 3.5MM, 2WAY")
      (fields (field (name "MANUFACTURER") "PHOENIX CONTACT") (field (name "PARTNUM") "1843606"))
      (libsource (lib "ea_Connectors") (part "MCV1.5/2-G-3.5"))
    )
    (comp (ref "X20")
      (value "MCV 1,5/ 2-G-3,5")
      (footprint "mcv1.5-2-g_3.5")
      (description "HEADER, VERTICAL, 3.5MM, 2WAY")
      (fields (field (name "MANUFACTURER") "PHOENIX CONTACT") (field (name "PARTNUM") "1843606"))
      (libsource (lib "ea_Connectors") (part "MCV1.5/2-G-3.5"))
    )
    (comp (ref "X21")
      (value "MCV 1,5/ 2-G-3,5")
      (footprint "mcv1.5-2-g_3.5")
      (description "HEADER, VERTICAL, 3.5MM, 2WAY")
      (fields (field (name "MANUFACTURER") "PHOENIX CONTACT") (field (name "PARTNUM") "1843606"))
      (libsource (lib "ea_Connectors") (part "MCV1.5/2-G-3.5"))
    )
    (comp (ref "X22")
      (value "MCV 1,5/ 2-G-3,5")
      (footprint "mcv1.5-2-g_3.5")
      (description "HEADER, VERTICAL, 3.5MM, 2WAY")
      (fields (field (name "MANUFACTURER") "PHOENIX CONTACT") (field (name "PARTNUM") "1843606"))
      (libsource (lib "ea_Connectors") (part "MCV1.5/2-G-3.5"))
    )
    (comp (ref "X24")
      (value "MCV 1,5/ 2-G-3,5")
      (footprint "mcv1.5-2-g_3.5")
      (description "HEADER, VERTICAL, 3.5MM, 2WAY")
      (fields (field (name "MANUFACTURER") "PHOENIX CONTACT") (field (name "PARTNUM") "1843606"))
      (libsource (lib "ea_Connectors") (part "MCV1.5/2-G-3.5"))
    )
    (comp (ref "X25")
      (value "MCV 1,5/ 2-G-3,5")
      (footprint "mcv1.5-2-g_3.5")
      (description "HEADER, VERTICAL, 3.5MM, 2WAY")
      (fields (field (name "MANUFACTURER") "PHOENIX CONTACT") (field (name "PARTNUM") "1843606"))
      (libsource (lib "ea_Connectors") (part "MCV1.5/2-G-3.5"))
    )
    (comp (ref "X27")
      (value "MCV 1,5/ 2-G-3,5")
      (footprint "mcv1.5-2-g_3.5")
      (description "HEADER, VERTICAL, 3.5MM, 2WAY")
      (fields (field (name "MANUFACTURER") "PHOENIX CONTACT") (field (name "PARTNUM") "1843606"))
      (libsource (lib "ea_Connectors") (part "MCV1.5/2-G-3.5"))
    )
    (comp (ref "X29")
      (value "MCV 1,5/ 2-G-3,5")
      (footprint "mcv1.5-2-g_3.5")
      (description "HEADER, VERTICAL, 3.5MM, 2WAY")
      (fields (field (name "MANUFACTURER") "PHOENIX CONTACT") (field (name "PARTNUM") "1843606"))
      (libsource (lib "ea_Connectors") (part "MCV1.5/2-G-3.5"))
    )
    (comp (ref "X30")
      (value "MCV 1,5/ 2-G-3,5")
      (footprint "mcv1.5-2-g_3.5")
      (description "HEADER, VERTICAL, 3.5MM, 2WAY")
      (fields (field (name "MANUFACTURER") "PHOENIX CONTACT") (field (name "PARTNUM") "1843606"))
      (libsource (lib "ea_Connectors") (part "MCV1.5/2-G-3.5"))
    )
    (comp (ref "X32")
      (value "MCV 1,5/ 2-G-3,5")
      (footprint "mcv1.5-2-g_3.5")
      (description "HEADER, VERTICAL, 3.5MM, 2WAY")
      (fields (field (name "MANUFACTURER") "PHOENIX CONTACT") (field (name "PARTNUM") "1843606"))
      (libsource (lib "ea_Connectors") (part "MCV1.5/2-G-3.5"))
    )
    (comp (ref "X39")
      (value "MCV 1,5/ 6-G-3,5")
      (footprint "mcv1.5-6-g_3.5")
      (description "HEADER, VERTICAL, 3.5MM, 6WAY")
      (fields (field (name "MANUFACTURER") "PHOENIX CONTACT") (field (name "PARTNUM") "1843648"))
      (libsource (lib "ea_Connectors") (part "MCV1.5/6-G-3.5"))
    )
    (comp (ref "X40")
      (value "MCV 1,5/ 2-G-3,5")
      (footprint "mcv1.5-2-g_3.5")
      (description "HEADER, VERTICAL, 3.5MM, 2WAY")
      (fields (field (name "MANUFACTURER") "PHOENIX CONTACT") (field (name "PARTNUM") "1843606"))
      (libsource (lib "ea_Connectors") (part "MCV1.5/2-G-3.5"))
    )
    (comp (ref "X41")
      (value "MCV 1,5/ 8-G-3,5")
      (footprint "mcv1.5-8-g_3.5")
      (description "HEADER, VERTICAL, 3.5MM, 8WAY")
      (fields (field (name "MANUFACTURER") "PHOENIX CONTACT") (field (name "PARTNUM") "1843664"))
      (libsource (lib "ea_Connectors") (part "MCV1.5/8-G-3.5"))
    )
    (comp (ref "X42")
      (value "MCV 1,5/ 3-G-3,5")
      (footprint "mcv1.5-3-g_3.5")
      (description "Header, 8 A, 160 V, 3.5 mm pitch, 3 pos")
      (fields (field (name "MANUFACTURER") "Phoenix Contact") (field (name "PARTNUM") "1843619"))
      (libsource (lib "ea_Connectors") (part "MCV1.5/3-G-3.5"))
    )
    (comp (ref "X43")
      (value "MCV 1,5/ 3-G-3,5")
      (footprint "mcv1.5-3-g_3.5")
      (description "Header, 8 A, 160 V, 3.5 mm pitch, 3 pos")
      (fields (field (name "MANUFACTURER") "Phoenix Contact") (field (name "PARTNUM") "1843619"))
      (libsource (lib "ea_Connectors") (part "MCV1.5/3-G-3.5"))
    )
  )
  (nets
    (net (code "1") (name "+3V3") (class "Default")
      (node (ref "R100") (pin "2") (pinfunction "2_2") (pintype "passive"))
      (node (ref "R101") (pin "2") (pinfunction "2_2") (pintype "passive"))
      (node (ref "R102") (pin "2") (pinfunction "2_2") (pintype "passive"))
      (node (ref "R109") (pin "2") (pinfunction "2_2") (pintype "passive"))
      (node (ref "R110") (pin "2") (pinfunction "2_2") (pintype "passive"))
      (node (ref "R68") (pin "1") (pinfunction "1_1") (pintype "passive"))
      (node (ref "R96") (pin "2") (pinfunction "2_2") (pintype "passive"))
      (node (ref "R97") (pin "2") (pinfunction "2_2") (pintype "passive"))
      (node (ref "R98") (pin "2") (pinfunction "2_2") (pintype "passive"))
      (node (ref "R99") (pin "2") (pinfunction "2_2") (pintype "passive"))
    )
    (net (code "2") (name "+5V") (class "Default")
      (node (ref "C72") (pin "2") (pinfunction "2_2") (pintype "passive"))
      (node (ref "C73") (pin "2") (pinfunction "2_2") (pintype "passive"))
      (node (ref "U12") (pin "2") (pinfunction "VCC_2") (pintype "passive"))
      (node (ref "U13") (pin "2") (pinfunction "VCC_2") (pintype "passive"))
    )
    (net (code "3") (name "+10V") (class "Default")
      (node (ref "C75") (pin "2") (pinfunction "2_2") (pintype "passive"))
      (node (ref "C81") (pin "2") (pinfunction "2_2") (pintype "passive"))
      (node (ref "U14") (pin "6") (pinfunction "VDD_6") (pintype "passive"))
      (node (ref "U18") (pin "7") (pinfunction "V+_7") (pintype "power_in"))
    )
    (net (code "4") (name "+24V") (class "Default")
      (node (ref "F2") (pin "2") (pinfunction "2_2") (pintype "passive"))
      (node (ref "F4") (pin "1") (pinfunction "1_1") (pintype "passive"))
      (node (ref "F7") (pin "2") (pinfunction "2_2") (pintype "passive"))
      (node (ref "J8") (pin "1") (pinfunction "1_1") (pintype "passive"))
      (node (ref "R106") (pin "2") (pinfunction "2_2") (pintype "passive"))
      (node (ref "R107") (pin "2") (pinfunction "2_2") (pintype "passive"))
      (node (ref "U12") (pin "1") (pinfunction "RS+_1") (pintype "passive"))
      (node (ref "U13") (pin "1") (pinfunction "RS+_1") (pintype "passive"))
    )
    (net (code "5") (name "/DAC1") (class "Default")
      (node (ref "R108") (pin "2") (pinfunction "2_2") (pintype "passive"))
    )
    (net (code "6") (name "/ESC1") (class "Default")
      (node (ref "C37") (pin "1") (pinfunction "1_1") (pintype "passive"))
      (node (ref "D25") (pin "2") (pintype "passive"))
      (node (ref "R66") (pin "2") (pinfunction "2_2") (pintype "passive"))
      (node (ref "R67") (pin "2") (pinfunction "2_2") (pintype "passive"))
    )
    (net (code "7") (name "/ESC2") (class "Default")
      (node (ref "C35") (pin "2") (pinfunction "2_2") (pintype "passive"))
      (node (ref "D25") (pin "1") (pintype "passive"))
      (node (ref "R64") (pin "2") (pinfunction "2_2") (pintype "passive"))
      (node (ref "R65") (pin "1") (pinfunction "1_1") (pintype "passive"))
    )
    (net (code "8") (name "/ESC3") (class "Default")
      (node (ref "C34") (pin "1") (pinfunction "1_1") (pintype "passive"))
      (node (ref "D24") (pin "2") (pintype "passive"))
      (node (ref "R62") (pin "2") (pinfunction "2_2") (pintype "passive"))
      (node (ref "R63") (pin "2") (pinfunction "2_2") (pintype "passive"))
    )
    (net (code "9") (name "/ESC4") (class "Default")
      (node (ref "C33") (pin "2") (pinfunction "2_2") (pintype "passive"))
      (node (ref "D24") (pin "1") (pintype "passive"))
      (node (ref "R58") (pin "2") (pinfunction "2_2") (pintype "passive"))
      (node (ref "R61") (pin "1") (pinfunction "1_1") (pintype "passive"))
    )
    (net (code "10") (name "/ESC5") (class "Default")
      (node (ref "C32") (pin "1") (pinfunction "1_1") (pintype "passive"))
      (node (ref "D23") (pin "2") (pintype "passive"))
      (node (ref "R55") (pin "2") (pinfunction "2_2") (pintype "passive"))
      (node (ref "R56") (pin "2") (pinfunction "2_2") (pintype "passive"))
    )
    (net (code "11") (name "/INVSTATE") (class "Default")
      (node (ref "C68") (pin "2") (pinfunction "2_2") (pintype "passive"))
      (node (ref "D28") (pin "2") (pintype "passive"))
      (node (ref "R87") (pin "1") (pinfunction "1_1") (pintype "passive"))
      (node (ref "R88") (pin "2") (pinfunction "2_2") (pintype "passive"))
    )
    (net (code "12") (name "/LAND1") (class "Default")
      (node (ref "C29") (pin "1") (pinfunction "1_1") (pintype "passive"))
      (node (ref "D20") (pin "2") (pintype "passive"))
      (node (ref "R51") (pin "2") (pinfunction "2_2") (pintype "passive"))
      (node (ref "R53") (pin "2") (pinfunction "2_2") (pintype "passive"))
    )
    (net (code "13") (name "/LAND1IN") (class "Default")
      (node (ref "R51") (pin "1") (pinfunction "1_1") (pintype "passive"))
      (node (ref "X15") (pin "2") (pinfunction "2_2") (pintype "passive"))
    )
    (net (code "14") (name "/LAND2") (class "Default")
      (node (ref "C28") (pin "2") (pinfunction "2_2") (pintype "passive"))
      (node (ref "D20") (pin "1") (pintype "passive"))
      (node (ref "R49") (pin "2") (pinfunction "2_2") (pintype "passive"))
      (node (ref "R50") (pin "1") (pinfunction "1_1") (pintype "passive"))
    )
    (net (code "15") (name "/LAND2IN") (class "Default")
      (node (ref "R49") (pin "1") (pinfunction "1_1") (pintype "passive"))
      (node (ref "X15") (pin "3") (pinfunction "3_3") (pintype "passive"))
    )
    (net (code "16") (name "/LAND3") (class "Default")
      (node (ref "C27") (pin "1") (pinfunction "1_1") (pintype "passive"))
      (node (ref "D19") (pin "2") (pintype "passive"))
      (node (ref "R47") (pin "2") (pinfunction "2_2") (pintype "passive"))
      (node (ref "R48") (pin "2") (pinfunction "2_2") (pintype "passive"))
    )
    (net (code "17") (name "/LAND3IN") (class "Default")
      (node (ref "R47") (pin "1") (pinfunction "1_1") (pintype "passive"))
      (node (ref "X15") (pin "4") (pinfunction "4_4") (pintype "passive"))
    )
    (net (code "18") (name "/LAND4") (class "Default")
      (node (ref "C25") (pin "2") (pinfunction "2_2") (pintype "passive"))
      (node (ref "D19") (pin "1") (pintype "passive"))
      (node (ref "R45") (pin "2") (pinfunction "2_2") (pintype "passive"))
      (node (ref "R46") (pin "1") (pinfunction "1_1") (pintype "passive"))
    )
    (net (code "19") (name "/LAND4IN") (class "Default")
      (node (ref "R45") (pin "1") (pinfunction "1_1") (pintype "passive"))
      (node (ref "X15") (pin "5") (pinfunction "5_5") (pintype "passive"))
    )
    (net (code "20") (name "/LAND5") (class "Default")
      (node (ref "C23") (pin "1") (pinfunction "1_1") (pintype "passive"))
      (node (ref "D15") (pin "2") (pintype "passive"))
      (node (ref "R43") (pin "2") (pinfunction "2_2") (pintype "passive"))
      (node (ref "R44") (pin "2") (pinfunction "2_2") (pintype "passive"))
    )
    (net (code "21") (name "/LAND5IN") (class "Default")
      (node (ref "R43") (pin "1") (pinfunction "1_1") (pintype "passive"))
      (node (ref "X15") (pin "6") (pinfunction "6_6") (pintype "passive"))
    )
    (net (code "22") (name "/LAND6") (class "Default")
      (node (ref "C22") (pin "2") (pinfunction "2_2") (pintype "passive"))
      (node (ref "D15") (pin "1") (pintype "passive"))
      (node (ref "R35") (pin "2") (pinfunction "2_2") (pintype "passive"))
      (node (ref "R37") (pin "1") (pinfunction "1_1") (pintype "passive"))
    )
    (net (code "23") (name "/LAND6IN") (class "Default")
      (node (ref "R35") (pin "1") (pinfunction "1_1") (pintype "passive"))
      (node (ref "X15") (pin "7") (pinfunction "7_7") (pintype "passive"))
    )
    (net (code "24") (name "/MISCSW1") (class "Default")
      (node (ref "C71") (pin "1") (pinfunction "1_1") (pintype "passive"))
      (node (ref "D30") (pin "1") (pintype "passive"))
      (node (ref "R89") (pin "2") (pinfunction "2_2") (pintype "passive"))
      (node (ref "R90") (pin "2") (pinfunction "2_2") (pintype "passive"))
    )
    (net (code "25") (name "/MISCSW2") (class "Default")
      (node (ref "C74") (pin "2") (pinfunction "2_2") (pintype "passive"))
      (node (ref "D30") (pin "2") (pintype "passive"))
      (node (ref "R91") (pin "1") (pinfunction "1_1") (pintype "passive"))
      (node (ref "R95") (pin "2") (pinfunction "2_2") (pintype "passive"))
    )
    (net (code "26") (name "/MOTOR_TEMP") (class "Default")
      (node (ref "C44") (pin "2") (pinfunction "2_2") (pintype "passive"))
      (node (ref "D23") (pin "1") (pintype "passive"))
      (node (ref "R70") (pin "2") (pinfunction "2_2") (pintype "passive"))
    )
    (net (code "27") (name "/OUT1") (class "Default")
      (node (ref "D32") (pin "2") (pinfunction "2_2") (pintype "passive"))
      (node (ref "U16") (pin "7") (pinfunction "IN7_7") (pintype "power_in"))
    )
    (net (code "28") (name "/OUT2") (class "Default")
      (node (ref "D33") (pin "2") (pinfunction "2_2") (pintype "passive"))
      (node (ref "U16") (pin "6") (pinfunction "IN6_6") (pintype "power_in"))
    )
    (net (code "29") (name "/OUT3") (class "Default")
      (node (ref "D34") (pin "2") (pinfunction "2_2") (pintype "passive"))
      (node (ref "U16") (pin "5") (pinfunction "IN5_5") (pintype "power_in"))
    )
    (net (code "30") (name "/OUT4") (class "Default")
      (node (ref "D35") (pin "2") (pinfunction "2_2") (pintype "passive"))
      (node (ref "U16") (pin "4") (pinfunction "IN4_4") (pintype "power_in"))
    )
    (net (code "31") (name "/OUT5") (class "Default")
      (node (ref "D36") (pin "2") (pinfunction "2_2") (pintype "passive"))
      (node (ref "U16") (pin "3") (pinfunction "IN3_3") (pintype "power_in"))
    )
    (net (code "32") (name "/OUT6") (class "Default")
      (node (ref "D37") (pin "2") (pinfunction "2_2") (pintype "passive"))
      (node (ref "U16") (pin "2") (pinfunction "IN2_2") (pintype "power_in"))
    )
    (net (code "33") (name "/OUT7") (class "Default")
      (node (ref "D38") (pin "2") (pinfunction "2_2") (pintype "passive"))
      (node (ref "U16") (pin "1") (pinfunction "IN1_1") (pintype "power_in"))
    )
    (net (code "34") (name "/PSENS1") (class "Default")
      (node (ref "R110") (pin "1") (pinfunction "1_1") (pintype "passive"))
      (node (ref "R112") (pin "1") (pinfunction "1_1") (pintype "passive"))
    )
    (net (code "35") (name "/PSENS2") (class "Default")
      (node (ref "R109") (pin "1") (pinfunction "1_1") (pintype "passive"))
      (node (ref "R111") (pin "1") (pinfunction "1_1") (pintype "passive"))
    )
    (net (code "36") (name "/PWM1") (class "Default")
      (node (ref "D39") (pin "1") (pinfunction "A_1") (pintype "passive"))
      (node (ref "Q4") (pin "4") (pinfunction "D_4") (pintype "passive"))
      (node (ref "X42") (pin "1") (pinfunction "-_1") (pintype "passive"))
    )
    (net (code "37") (name "/PWM2") (class "Default")
      (node (ref "D40") (pin "1") (pinfunction "A_1") (pintype "passive"))
      (node (ref "Q5") (pin "4") (pinfunction "D_4") (pintype "passive"))
      (node (ref "X43") (pin "1") (pinfunction "-_1") (pintype "passive"))
    )
    (net (code "38") (name "/PWMP1") (class "Default")
      (node (ref "C86") (pin "2") (pinfunction "2_2") (pintype "passive"))
      (node (ref "D39") (pin "2") (pinfunction "C_2") (pintype "passive"))
      (node (ref "R106") (pin "1") (pinfunction "1_1") (pintype "passive"))
      (node (ref "U13") (pin "8") (pinfunction "RS-_8") (pintype "passive"))
      (node (ref "X42") (pin "2") (pinfunction "-_2") (pintype "passive"))
    )
    (net (code "39") (name "/PWMP2") (class "Default")
      (node (ref "C87") (pin "2") (pinfunction "2_2") (pintype "passive"))
      (node (ref "D40") (pin "2") (pinfunction "C_2") (pintype "passive"))
      (node (ref "R107") (pin "1") (pinfunction "1_1") (pintype "passive"))
      (node (ref "U12") (pin "8") (pinfunction "RS-_8") (pintype "passive"))
      (node (ref "X43") (pin "2") (pinfunction "-_2") (pintype "passive"))
    )
    (net (code "40") (name "/REFSW") (class "Default")
      (node (ref "C67") (pin "1") (pinfunction "1_1") (pintype "passive"))
      (node (ref "D28") (pin "1") (pintype "passive"))
      (node (ref "R83") (pin "2") (pinfunction "2_2") (pintype "passive"))
      (node (ref "R86") (pin "2") (pinfunction "2_2") (pintype "passive"))
    )
    (net (code "41") (name "/SAFETY_END") (class "Default")
      (node (ref "R56") (pin "1") (pinfunction "1_1") (pintype "passive"))
    )
    (net (code "42") (name "/SAFETY_IN") (class "Default")
      (node (ref "R67") (pin "1") (pinfunction "1_1") (pintype "passive"))
      (node (ref "X21") (pin "1") (pinfunction "1_1") (pintype "passive"))
    )
    (net (code "43") (name "/SAFETY_OUT") (class "Default")
      (node (ref "X18") (pin "2") (pinfunction "2_2") (pintype "passive"))
    )
    (net (code "44") (name "/SOL1_STATE") (class "Default")
      (node (ref "C70") (pin "1") (pinfunction "1_1") (pintype "passive"))
      (node (ref "D29") (pin "2") (pintype "passive"))
      (node (ref "R94") (pin "1") (pinfunction "1_1") (pintype "passive"))
    )
    (net (code "45") (name "/SOL2_STATE") (class "Default")
      (node (ref "C69") (pin "2") (pinfunction "2_2") (pintype "passive"))
      (node (ref "D29") (pin "1") (pintype "passive"))
      (node (ref "R93") (pin "1") (pinfunction "1_1") (pintype "passive"))
    )
    (net (code "46") (name "/SOLENOID1") (class "Default")
      (node (ref "U14") (pin "2") (pinfunction "INA_2") (pintype "passive"))
    )
    (net (code "47") (name "/SOLENOID2") (class "Default")
      (node (ref "U14") (pin "4") (pinfunction "INB_4") (pintype "passive"))
    )
    (net (code "48") (name "/UPLSW") (class "Default")
      (node (ref "C51") (pin "1") (pinfunction "1_1") (pintype "passive"))
      (node (ref "D27") (pin "1") (pintype "passive"))
      (node (ref "R72") (pin "2") (pinfunction "2_2") (pintype "passive"))
      (node (ref "R73") (pin "2") (pinfunction "2_2") (pintype "passive"))
    )
    (net (code "49") (name "/WEARSW") (class "Default")
      (node (ref "C54") (pin "2") (pinfunction "2_2") (pintype "passive"))
      (node (ref "D27") (pin "2") (pintype "passive"))
      (node (ref "R74") (pin "1") (pinfunction "1_1") (pintype "passive"))
      (node (ref "R75") (pin "2") (pinfunction "2_2") (pintype "passive"))
    )
    (net (code "50") (name "GND") (class "Default")
      (node (ref "C22") (pin "1") (pinfunction "1_1") (pintype "passive"))
      (node (ref "C23") (pin "2") (pinfunction "2_2") (pintype "passive"))
      (node (ref "C25") (pin "1") (pinfunction "1_1") (pintype "passive"))
      (node (ref "C27") (pin "2") (pinfunction "2_2") (pintype "passive"))
      (node (ref "C28") (pin "1") (pinfunction "1_1") (pintype "passive"))
      (node (ref "C29") (pin "2") (pinfunction "2_2") (pintype "passive"))
      (node (ref "C32") (pin "2") (pinfunction "2_2") (pintype "passive"))
      (node (ref "C33") (pin "1") (pinfunction "1_1") (pintype "passive"))
      (node (ref "C34") (pin "2") (pinfunction "2_2") (pintype "passive"))
      (node (ref "C35") (pin "1") (pinfunction "1_1") (pintype "passive"))
      (node (ref "C37") (pin "2") (pinfunction "2_2") (pintype "passive"))
      (node (ref "C44") (pin "1") (pinfunction "1_1") (pintype "passive"))
      (node (ref "C51") (pin "2") (pinfunction "2_2") (pintype "passive"))
      (node (ref "C54") (pin "1") (pinfunction "1_1") (pintype "passive"))
      (node (ref "C67") (pin "2") (pinfunction "2_2") (pintype "passive"))
      (node (ref "C68") (pin "1") (pinfunction "1_1") (pintype "passive"))
      (node (ref "C69") (pin "1") (pinfunction "1_1") (pintype "passive"))
      (node (ref "C70") (pin "2") (pinfunction "2_2") (pintype "passive"))
      (node (ref "C71") (pin "2") (pinfunction "2_2") (pintype "passive"))
      (node (ref "C72") (pin "1") (pinfunction "1_1") (pintype "passive"))
      (node (ref "C73") (pin "1") (pinfunction "1_1") (pintype "passive"))
      (node (ref "C74") (pin "1") (pinfunction "1_1") (pintype "passive"))
      (node (ref "C75") (pin "1") (pinfunction "1_1") (pintype "passive"))
      (node (ref "C81") (pin "1") (pinfunction "1_1") (pintype "passive"))
      (node (ref "C85") (pin "2") (pinfunction "2_2") (pintype "passive"))
      (node (ref "C86") (pin "1") (pinfunction "1_1") (pintype "passive"))
      (node (ref "C87") (pin "1") (pinfunction "1_1") (pintype "passive"))
      (node (ref "D15") (pin "3") (pintype "passive"))
      (node (ref "D19") (pin "3") (pintype "passive"))
      (node (ref "D20") (pin "3") (pintype "passive"))
      (node (ref "D23") (pin "3") (pintype "passive"))
      (node (ref "D24") (pin "3") (pintype "passive"))
      (node (ref "D25") (pin "3") (pintype "passive"))
      (node (ref "D27") (pin "3") (pintype "passive"))
      (node (ref "D28") (pin "3") (pintype "passive"))
      (node (ref "D29") (pin "3") (pintype "passive"))
      (node (ref "D30") (pin "3") (pintype "passive"))
      (node (ref "D41") (pin "3") (pintype "passive"))
      (node (ref "Q4") (pin "3") (pinfunction "S_3") (pintype "passive"))
      (node (ref "Q5") (pin "3") (pinfunction "S_3") (pintype "passive"))
      (node (ref "R113") (pin "2") (pinfunction "2_2") (pintype "passive"))
      (node (ref "R37") (pin "2") (pinfunction "2_2") (pintype "passive"))
      (node (ref "R44") (pin "1") (pinfunction "1_1") (pintype "passive"))
      (node (ref "R46") (pin "2") (pinfunction "2_2") (pintype "passive"))
      (node (ref "R48") (pin "1") (pinfunction "1_1") (pintype "passive"))
      (node (ref "R50") (pin "2") (pinfunction "2_2") (pintype "passive"))
      (node (ref "R53") (pin "1") (pinfunction "1_1") (pintype "passive"))
      (node (ref "R55") (pin "1") (pinfunction "1_1") (pintype "passive"))
      (node (ref "R61") (pin "2") (pinfunction "2_2") (pintype "passive"))
      (node (ref "R62") (pin "1") (pinfunction "1_1") (pintype "passive"))
      (node (ref "R65") (pin "2") (pinfunction "2_2") (pintype "passive"))
      (node (ref "R66") (pin "1") (pinfunction "1_1") (pintype "passive"))
      (node (ref "R73") (pin "1") (pinfunction "1_1") (pintype "passive"))
      (node (ref "R74") (pin "2") (pinfunction "2_2") (pintype "passive"))
      (node (ref "R86") (pin "1") (pinfunction "1_1") (pintype "passive"))
      (node (ref "R87") (pin "2") (pinfunction "2_2") (pintype "passive"))
      (node (ref "R90") (pin "1") (pinfunction "1_1") (pintype "passive"))
      (node (ref "R91") (pin "2") (pinfunction "2_2") (pintype "passive"))
      (node (ref "U12") (pin "4") (pinfunction "GND_4") (pintype "passive"))
      (node (ref "U13") (pin "4") (pinfunction "GND_4") (pintype "passive"))
      (node (ref "U14") (pin "3") (pinfunction "GND_3") (pintype "passive"))
      (node (ref "U16") (pin "8") (pinfunction "GND_8") (pintype "power_in"))
      (node (ref "U18") (pin "4") (pinfunction "GND_4") (pintype "power_in"))
      (node (ref "X15") (pin "8") (pinfunction "8_8") (pintype "passive"))
      (node (ref "X22") (pin "2") (pinfunction "2_2") (pintype "passive"))
      (node (ref "X39") (pin "3") (pinfunction "3_3") (pintype "passive"))
      (node (ref "X39") (pin "6") (pinfunction "6_6") (pintype "passive"))
      (node (ref "X40") (pin "2") (pinfunction "2_2") (pintype "passive"))
      (node (ref "X41") (pin "8") (pinfunction "8_8") (pintype "passive"))
      (node (ref "X42") (pin "3") (pinfunction "-_3") (pintype "passive"))
      (node (ref "X43") (pin "3") (pinfunction "-_3") (pintype "passive"))
    )
    (net (code "51") (name "Net-(D32-Pad1)") (class "Default")
      (node (ref "D32") (pin "1") (pinfunction "1_1") (pintype "passive"))
      (node (ref "R96") (pin "1") (pinfunction "1_1") (pintype "passive"))
    )
    (net (code "52") (name "Net-(D33-Pad1)") (class "Default")
      (node (ref "D33") (pin "1") (pinfunction "1_1") (pintype "passive"))
      (node (ref "R97") (pin "1") (pinfunction "1_1") (pintype "passive"))
    )
    (net (code "53") (name "Net-(D34-Pad1)") (class "Default")
      (node (ref "D34") (pin "1") (pinfunction "1_1") (pintype "passive"))
      (node (ref "R98") (pin "1") (pinfunction "1_1") (pintype "passive"))
    )
    (net (code "54") (name "Net-(D35-Pad1)") (class "Default")
      (node (ref "D35") (pin "1") (pinfunction "1_1") (pintype "passive"))
      (node (ref "R99") (pin "1") (pinfunction "1_1") (pintype "passive"))
    )
    (net (code "55") (name "Net-(D36-Pad1)") (class "Default")
      (node (ref "D36") (pin "1") (pinfunction "1_1") (pintype "passive"))
      (node (ref "R100") (pin "1") (pinfunction "1_1") (pintype "passive"))
    )
    (net (code "56") (name "Net-(D37-Pad1)") (class "Default")
      (node (ref "D37") (pin "1") (pinfunction "1_1") (pintype "passive"))
      (node (ref "R101") (pin "1") (pinfunction "1_1") (pintype "passive"))
    )
    (net (code "57") (name "Net-(D38-Pad1)") (class "Default")
      (node (ref "D38") (pin "1") (pinfunction "1_1") (pintype "passive"))
      (node (ref "R102") (pin "1") (pinfunction "1_1") (pintype "passive"))
    )
    (net (code "58") (name "Net-(D41-Pad1)") (class "Default")
      (node (ref "D41") (pin "1") (pintype "passive"))
      (node (ref "R111") (pin "2") (pinfunction "2_2") (pintype "passive"))
      (node (ref "X39") (pin "5") (pinfunction "5_5") (pintype "passive"))
    )
    (net (code "59") (name "Net-(D41-Pad2)") (class "Default")
      (node (ref "D41") (pin "2") (pintype "passive"))
      (node (ref "R112") (pin "2") (pinfunction "2_2") (pintype "passive"))
      (node (ref "X39") (pin "2") (pinfunction "2_2") (pintype "passive"))
    )
    (net (code "60") (name "Net-(F2-Pad1)") (class "Default")
      (node (ref "F2") (pin "1") (pinfunction "1_1") (pintype "passive"))
      (node (ref "X15") (pin "1") (pinfunction "1_1") (pintype "passive"))
    )
    (net (code "61") (name "Net-(F4-Pad2)") (class "Default")
      (node (ref "F4") (pin "2") (pinfunction "2_2") (pintype "passive"))
      (node (ref "X24") (pin "1") (pinfunction "1_1") (pintype "passive"))
      (node (ref "X25") (pin "1") (pinfunction "1_1") (pintype "passive"))
      (node (ref "X27") (pin "1") (pinfunction "1_1") (pintype "passive"))
      (node (ref "X29") (pin "1") (pinfunction "1_1") (pintype "passive"))
      (node (ref "X30") (pin "1") (pinfunction "1_1") (pintype "passive"))
      (node (ref "X32") (pin "1") (pinfunction "1_1") (pintype "passive"))
    )
    (net (code "62") (name "Net-(F7-Pad1)") (class "Default")
      (node (ref "F7") (pin "1") (pinfunction "1_1") (pintype "passive"))
      (node (ref "X39") (pin "1") (pinfunction "1_1") (pintype "passive"))
      (node (ref "X39") (pin "4") (pinfunction "4_4") (pintype "passive"))
    )
    (net (code "63") (name "Net-(Q4-G)") (class "Default")
      (node (ref "Q4") (pin "1") (pinfunction "G_1") (pintype "passive"))
      (node (ref "R103") (pin "2") (pinfunction "2_2") (pintype "passive"))
    )
    (net (code "64") (name "Net-(Q5-G)") (class "Default")
      (node (ref "Q5") (pin "1") (pinfunction "G_1") (pintype "passive"))
      (node (ref "R104") (pin "2") (pinfunction "2_2") (pintype "passive"))
    )
    (net (code "65") (name "Net-(R58-Pad1)") (class "Default")
      (node (ref "R58") (pin "1") (pinfunction "1_1") (pintype "passive"))
      (node (ref "X18") (pin "1") (pinfunction "1_1") (pintype "passive"))
      (node (ref "X19") (pin "2") (pinfunction "2_2") (pintype "passive"))
    )
    (net (code "66") (name "Net-(R63-Pad1)") (class "Default")
      (node (ref "R63") (pin "1") (pinfunction "1_1") (pintype "passive"))
      (node (ref "X19") (pin "1") (pinfunction "1_1") (pintype "passive"))
      (node (ref "X20") (pin "2") (pinfunction "2_2") (pintype "passive"))
    )
    (net (code "67") (name "Net-(R64-Pad1)") (class "Default")
      (node (ref "R64") (pin "1") (pinfunction "1_1") (pintype "passive"))
      (node (ref "X20") (pin "1") (pinfunction "1_1") (pintype "passive"))
      (node (ref "X21") (pin "2") (pinfunction "2_2") (pintype "passive"))
    )
    (net (code "68") (name "Net-(R68-Pad2)") (class "Default")
      (node (ref "R68") (pin "2") (pinfunction "2_2") (pintype "passive"))
      (node (ref "R70") (pin "1") (pinfunction "1_1") (pintype "passive"))
      (node (ref "X22") (pin "1") (pinfunction "1_1") (pintype "passive"))
    )
    (net (code "69") (name "Net-(R72-Pad1)") (class "Default")
      (node (ref "R72") (pin "1") (pinfunction "1_1") (pintype "passive"))
      (node (ref "X24") (pin "2") (pinfunction "2_2") (pintype "passive"))
    )
    (net (code "70") (name "Net-(R75-Pad1)") (class "Default")
      (node (ref "R75") (pin "1") (pinfunction "1_1") (pintype "passive"))
      (node (ref "X25") (pin "2") (pinfunction "2_2") (pintype "passive"))
    )
    (net (code "71") (name "Net-(R83-Pad1)") (class "Default")
      (node (ref "R83") (pin "1") (pinfunction "1_1") (pintype "passive"))
      (node (ref "X27") (pin "2") (pinfunction "2_2") (pintype "passive"))
    )
    (net (code "72") (name "Net-(R88-Pad1)") (class "Default")
      (node (ref "R88") (pin "1") (pinfunction "1_1") (pintype "passive"))
      (node (ref "X29") (pin "2") (pinfunction "2_2") (pintype "passive"))
    )
    (net (code "73") (name "Net-(R89-Pad1)") (class "Default")
      (node (ref "R89") (pin "1") (pinfunction "1_1") (pintype "passive"))
      (node (ref "X30") (pin "2") (pinfunction "2_2") (pintype "passive"))
    )
    (net (code "74") (name "Net-(R95-Pad1)") (class "Default")
      (node (ref "R95") (pin "1") (pinfunction "1_1") (pintype "passive"))
      (node (ref "X32") (pin "2") (pinfunction "2_2") (pintype "passive"))
    )
    (net (code "75") (name "Net-(R115-Pad2)") (class "Default")
      (node (ref "R115") (pin "2") (pinfunction "2_2") (pintype "passive"))
      (node (ref "X40") (pin "1") (pinfunction "1_1") (pintype "passive"))
    )
    (net (code "76") (name "Net-(U12-OUT)") (class "Default")
      (node (ref "R93") (pin "2") (pinfunction "2_2") (pintype "passive"))
      (node (ref "U12") (pin "5") (pinfunction "OUT_5") (pintype "passive"))
    )
    (net (code "77") (name "Net-(U13-OUT)") (class "Default")
      (node (ref "R94") (pin "2") (pinfunction "2_2") (pintype "passive"))
      (node (ref "U13") (pin "5") (pinfunction "OUT_5") (pintype "passive"))
    )
    (net (code "78") (name "Net-(U14-OUTA)") (class "Default")
      (node (ref "R103") (pin "1") (pinfunction "1_1") (pintype "passive"))
      (node (ref "U14") (pin "7") (pinfunction "OUTA_7") (pintype "passive"))
    )
    (net (code "79") (name "Net-(U14-OUTB)") (class "Default")
      (node (ref "R104") (pin "1") (pinfunction "1_1") (pintype "passive"))
      (node (ref "U14") (pin "5") (pinfunction "OUTB_5") (pintype "passive"))
    )
    (net (code "80") (name "Net-(U16-COMD)") (class "Default")
      (node (ref "J8") (pin "2") (pinfunction "2_2") (pintype "passive"))
      (node (ref "U16") (pin "9") (pinfunction "COMD_9") (pintype "power_in"))
    )
    (net (code "81") (name "Net-(U16-OUT1)") (class "Default")
      (node (ref "U16") (pin "16") (pinfunction "OUT1_16") (pintype "power_in"))
      (node (ref "X41") (pin "1") (pinfunction "1_1") (pintype "passive"))
    )
    (net (code "82") (name "Net-(U16-OUT2)") (class "Default")
      (node (ref "U16") (pin "15") (pinfunction "OUT2_15") (pintype "power_in"))
      (node (ref "X41") (pin "2") (pinfunction "2_2") (pintype "passive"))
    )
    (net (code "83") (name "Net-(U16-OUT3)") (class "Default")
      (node (ref "U16") (pin "14") (pinfunction "OUT3_14") (pintype "power_in"))
      (node (ref "X41") (pin "3") (pinfunction "3_3") (pintype "passive"))
    )
    (net (code "84") (name "Net-(U16-OUT4)") (class "Default")
      (node (ref "U16") (pin "13") (pinfunction "OUT4_13") (pintype "power_in"))
      (node (ref "X41") (pin "4") (pinfunction "4_4") (pintype "passive"))
    )
    (net (code "85") (name "Net-(U16-OUT5)") (class "Default")
      (node (ref "U16") (pin "12") (pinfunction "OUT5_12") (pintype "power_in"))
      (node (ref "X41") (pin "5") (pinfunction "5_5") (pintype "passive"))
    )
    (net (code "86") (name "Net-(U16-OUT6)") (class "Default")
      (node (ref "U16") (pin "11") (pinfunction "OUT6_11") (pintype "power_in"))
      (node (ref "X41") (pin "6") (pinfunction "6_6") (pintype "passive"))
    )
    (net (code "87") (name "Net-(U16-OUT7)") (class "Default")
      (node (ref "U16") (pin "10") (pinfunction "OUT7_10") (pintype "power_in"))
      (node (ref "X41") (pin "7") (pinfunction "7_7") (pintype "passive"))
    )
    (net (code "88") (name "Net-(U18-IN+)") (class "Default")
      (node (ref "C85") (pin "1") (pinfunction "1_1") (pintype "passive"))
      (node (ref "R108") (pin "1") (pinfunction "1_1") (pintype "passive"))
      (node (ref "U18") (pin "3") (pinfunction "IN+_3") (pintype "passive"))
    )
    (net (code "89") (name "Net-(U18-IN-)") (class "Default")
      (node (ref "R113") (pin "1") (pinfunction "1_1") (pintype "passive"))
      (node (ref "R114") (pin "1") (pinfunction "1_1") (pintype "passive"))
      (node (ref "U18") (pin "2") (pinfunction "IN-_2") (pintype "passive"))
    )
    (net (code "90") (name "Net-(U18-OUT)") (class "Default")
      (node (ref "R114") (pin "2") (pinfunction "2_2") (pintype "passive"))
      (node (ref "R115") (pin "1") (pinfunction "1_1") (pintype "passive"))
      (node (ref "U18") (pin "6") (pinfunction "OUT_6") (pintype "passive"))
    )
  )
)
